# MMC_2_2_Ethernet.net
KiCad netlist of a schematic drawn in Altium Designer
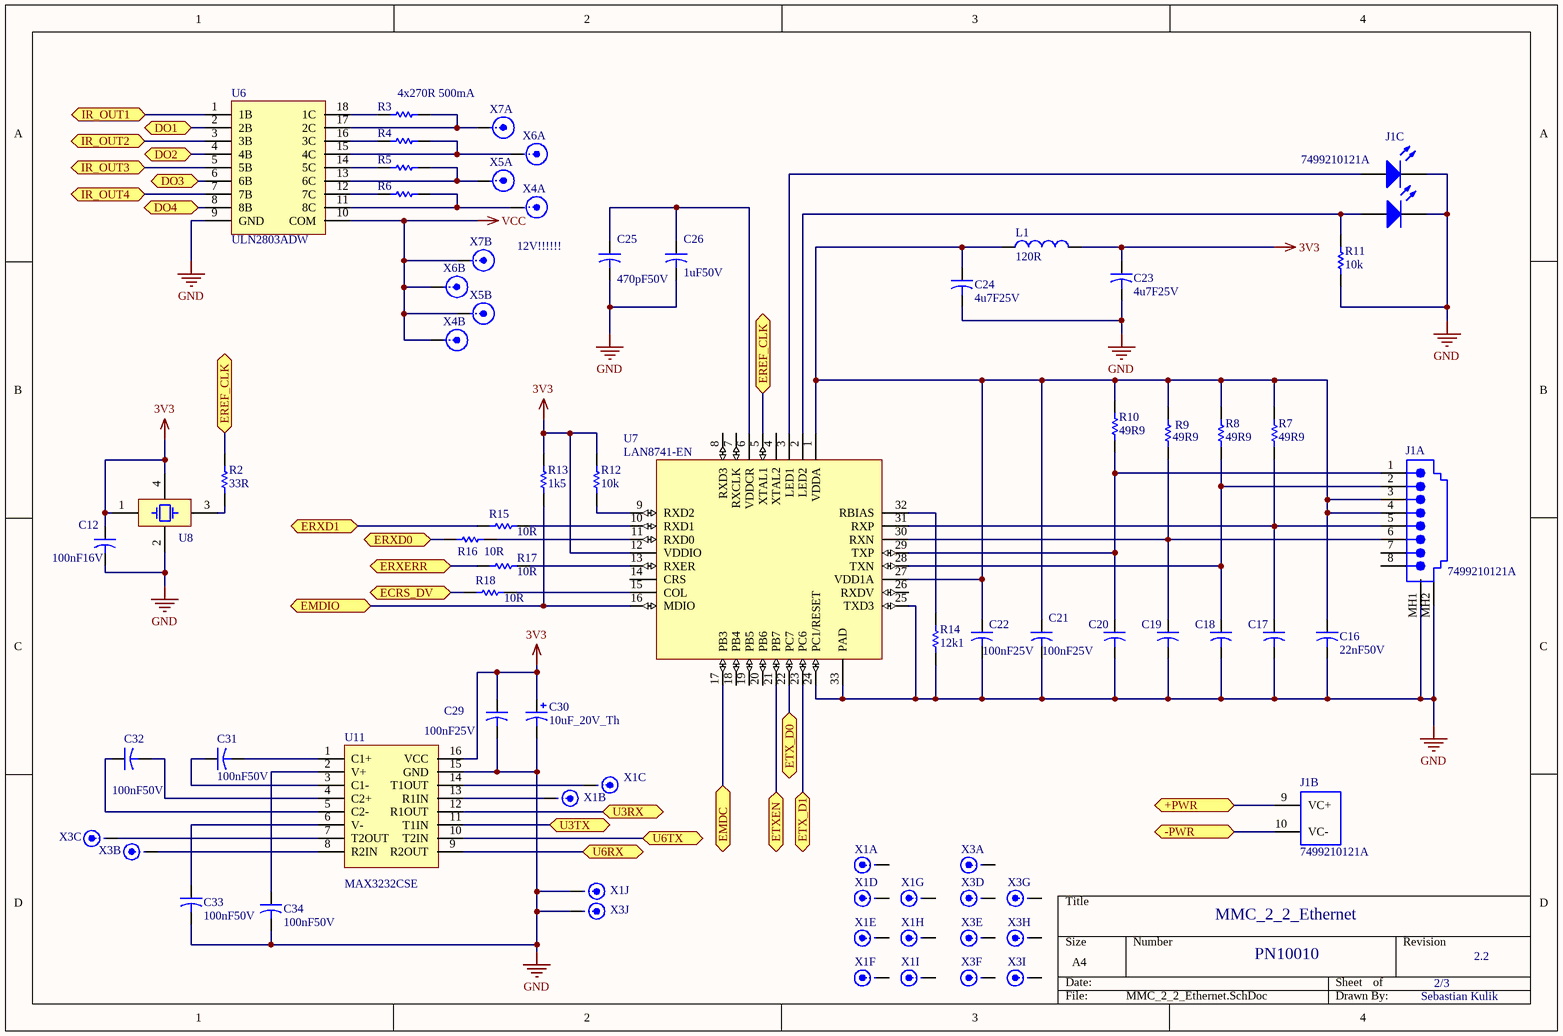
[diagram p0: MMC_2_2_Ethernet.SchDoc]

(export (version "E")
  (design (tool "Eeschema 10.0.6"))
  (components
    (comp (ref "C12")
      (value "100nF16V")
      (footprint "C0402")
      (description "Capacitor")
      (fields
        (field (name "MANUFACTURER") "TDK")
        (field (name "Comment") "100nF16V_0402")
        (field (name "PUBLISHER") "Sebastian Kulik")
      )
      (libsource (lib "Capacitors") (part "100nF16V_0402"))
    )
    (comp (ref "C16")
      (value "22nF50V")
      (footprint "C0603")
      (description "AVX ,  X7R, 5%, 50V")
      (fields
        (field (name "MANUFACTURER") "AVX")
        (field (name "Comment") "22nF50V_0603")
        (field (name "PUBLISHER") "Sebastian Kulik")
      )
      (libsource (lib "Capacitors") (part "22nF50V_0603"))
    )
    (comp (ref "C17")
      (value "10pF50V_0603")
      (footprint "C0603")
      (description "AVX ,  +-0.5pF, 50V")
      (fields (field (name "MANUFACTURER") "AVX") (field (name "PUBLISHER") "Sebastian Kulik"))
      (libsource (lib "Capacitors") (part "10pF50V_0603"))
    )
    (comp (ref "C18")
      (value "10pF50V_0603")
      (footprint "C0603")
      (description "AVX ,  +-0.5pF, 50V")
      (fields (field (name "MANUFACTURER") "AVX") (field (name "PUBLISHER") "Sebastian Kulik"))
      (libsource (lib "Capacitors") (part "10pF50V_0603"))
    )
    (comp (ref "C19")
      (value "10pF50V_0603")
      (footprint "C0603")
      (description "AVX ,  +-0.5pF, 50V")
      (fields (field (name "MANUFACTURER") "AVX") (field (name "PUBLISHER") "Sebastian Kulik"))
      (libsource (lib "Capacitors") (part "10pF50V_0603"))
    )
    (comp (ref "C20")
      (value "10pF50V_0603")
      (footprint "C0603")
      (description "AVX ,  +-0.5pF, 50V")
      (fields (field (name "MANUFACTURER") "AVX") (field (name "PUBLISHER") "Sebastian Kulik"))
      (libsource (lib "Capacitors") (part "10pF50V_0603"))
    )
    (comp (ref "C21")
      (value "100nF25V")
      (footprint "C0402")
      (description "AVX, X5R, 10%, 25V")
      (fields
        (field (name "MANUFACTURER") "AVX")
        (field (name "Comment") "100nF25V_0402")
        (field (name "PUBLISHER") "Sebastian Kulik")
      )
      (libsource (lib "Capacitors") (part "100nF25V_0402"))
    )
    (comp (ref "C22")
      (value "100nF25V")
      (footprint "C0402")
      (description "AVX, X5R, 10%, 25V")
      (fields
        (field (name "MANUFACTURER") "AVX")
        (field (name "Comment") "100nF25V_0402")
        (field (name "PUBLISHER") "Sebastian Kulik")
      )
      (libsource (lib "Capacitors") (part "100nF25V_0402"))
    )
    (comp (ref "C23")
      (value "4u7F25V")
      (footprint "C0805")
      (description "TDK  C series, X7R, 10%, 25V")
      (fields
        (field (name "MANUFACTURER") "TDK")
        (field (name "Comment") "4u7F25V_0805")
        (field (name "PUBLISHER") "Sebastian Kulik")
      )
      (libsource (lib "Capacitors") (part "4u7F25V_0805"))
    )
    (comp (ref "C24")
      (value "4u7F25V")
      (footprint "C0805")
      (description "TDK  C series, X7R, 10%, 25V")
      (fields
        (field (name "MANUFACTURER") "TDK")
        (field (name "Comment") "4u7F25V_0805")
        (field (name "PUBLISHER") "Sebastian Kulik")
      )
      (libsource (lib "Capacitors") (part "4u7F25V_0805"))
    )
    (comp (ref "C25")
      (value "470pF50V")
      (footprint "C0402")
      (description "AVX, 50V")
      (fields
        (field (name "MANUFACTURER") "AVX")
        (field (name "Comment") "470pF50V_0402")
        (field (name "PUBLISHER") "Sebastian Kulik")
      )
      (libsource (lib "Capacitors") (part "470pF50V_0402"))
    )
    (comp (ref "C26")
      (value "1uF50V")
      (footprint "C0603")
      (description "C series, X5R, 10%")
      (fields
        (field (name "MANUFACTURER") "TDK")
        (field (name "Comment") "1uF50V_0603")
        (field (name "PUBLISHER") "Sebastian Kulik")
      )
      (libsource (lib "Capacitors") (part "1uF50V_0603"))
    )
    (comp (ref "C29")
      (value "100nF25V")
      (footprint "C0402")
      (description "AVX, X5R, 10%, 25V")
      (fields
        (field (name "MANUFACTURER") "AVX")
        (field (name "Comment") "100nF25V_0402")
        (field (name "PUBLISHER") "Sebastian Kulik")
      )
      (libsource (lib "Capacitors") (part "100nF25V_0402"))
    )
    (comp (ref "C30")
      (value "10uF_20V_Th")
      (footprint "Vishay293D-B")
      (description "293 series, tantal, 10%, 10V")
      (fields
        (field (name "MANUFACTURER") "Vishay")
        (field (name "Comment") "10uF_20V_V293D-B")
        (field (name "PUBLISHER") "Sebastian Kulik")
      )
      (libsource (lib "Capacitors") (part "10uF_20V_V293D-B"))
    )
    (comp (ref "C31")
      (value "100nF50V")
      (footprint "C0402")
      (description "C series, X5R, 10%, 50V")
      (fields
        (field (name "MANUFACTURER") "TDK")
        (field (name "Comment") "100n50V_0402")
        (field (name "PUBLISHER") "Sebastian Kulik")
      )
      (libsource (lib "Capacitors") (part "100n50V_0402"))
    )
    (comp (ref "C32")
      (value "100nF50V")
      (footprint "C0402")
      (description "C series, X5R, 10%, 50V")
      (fields
        (field (name "MANUFACTURER") "TDK")
        (field (name "Comment") "100n50V_0402")
        (field (name "PUBLISHER") "Sebastian Kulik")
      )
      (libsource (lib "Capacitors") (part "100n50V_0402"))
    )
    (comp (ref "C33")
      (value "100nF50V")
      (footprint "C0402")
      (description "C series, X5R, 10%, 50V")
      (fields
        (field (name "MANUFACTURER") "TDK")
        (field (name "Comment") "100n50V_0402")
        (field (name "PUBLISHER") "Sebastian Kulik")
      )
      (libsource (lib "Capacitors") (part "100n50V_0402"))
    )
    (comp (ref "C34")
      (value "100nF50V")
      (footprint "C0402")
      (description "C series, X5R, 10%, 50V")
      (fields
        (field (name "MANUFACTURER") "TDK")
        (field (name "Comment") "100n50V_0402")
        (field (name "PUBLISHER") "Sebastian Kulik")
      )
      (libsource (lib "Capacitors") (part "100n50V_0402"))
    )
    (comp (ref "J1")
      (value "7499210121A")
      (footprint "7499210121A")
      (description "Modular Jack , Right Angle RJ-45, Low Profile")
      (fields (field (name "MANUFACTURER") "Wuerth Elektronik") (field (name "PUBLISHER") "Sebastian Kulik"))
      (libsource (lib "Connectors") (part "Ethernet, POE, WE7499210121A"))
    )
    (comp (ref "L1")
      (value "120R")
      (footprint "L0603")
      (description "Murata, Ferrit, 120Rx2A")
      (fields
        (field (name "MANUFACTURER") "Murata")
        (field (name "Comment") "120R4A_0603")
        (field (name "PUBLISHER") "Sebastian Kulik")
      )
      (libsource (lib "Passives") (part "120R4A_0603"))
    )
    (comp (ref "R2")
      (value "33R")
      (footprint "R0402")
      (description "Vishay CRCW series, 63mW, 1%")
      (fields
        (field (name "MANUFACTURER") "Vishay")
        (field (name "Comment") "33R_0402")
        (field (name "PUBLISHER") "Sebastian Kulik")
      )
      (libsource (lib "Resistors") (part "33R_0402"))
    )
    (comp (ref "R3")
      (value "270R_1210")
      (footprint "R1210_N")
      (description "ERJ series, 500mW, 5%")
      (fields (field (name "MANUFACTURER") "Panasonic") (field (name "PUBLISHER") "Sebastian Kulik"))
      (libsource (lib "Resistors") (part "270R_1210"))
    )
    (comp (ref "R4")
      (value "270R_1210")
      (footprint "R1210_N")
      (description "ERJ series, 500mW, 5%")
      (fields (field (name "MANUFACTURER") "Panasonic") (field (name "PUBLISHER") "Sebastian Kulik"))
      (libsource (lib "Resistors") (part "270R_1210"))
    )
    (comp (ref "R5")
      (value "270R_1210")
      (footprint "R1210_N")
      (description "ERJ series, 500mW, 5%")
      (fields (field (name "MANUFACTURER") "Panasonic") (field (name "PUBLISHER") "Sebastian Kulik"))
      (libsource (lib "Resistors") (part "270R_1210"))
    )
    (comp (ref "R6")
      (value "270R_1210")
      (footprint "R1210_N")
      (description "ERJ series, 500mW, 5%")
      (fields (field (name "MANUFACTURER") "Panasonic") (field (name "PUBLISHER") "Sebastian Kulik"))
      (libsource (lib "Resistors") (part "270R_1210"))
    )
    (comp (ref "R7")
      (value "49R9")
      (footprint "R0402")
      (description "Vishay CRCW series, 63mW, 1%")
      (fields
        (field (name "MANUFACTURER") "Vishay")
        (field (name "Comment") "49R9_0402")
        (field (name "PUBLISHER") "Sebastian Kulik")
      )
      (libsource (lib "Resistors") (part "49R9_0402"))
    )
    (comp (ref "R8")
      (value "49R9")
      (footprint "R0402")
      (description "Vishay CRCW series, 63mW, 1%")
      (fields
        (field (name "MANUFACTURER") "Vishay")
        (field (name "Comment") "49R9_0402")
        (field (name "PUBLISHER") "Sebastian Kulik")
      )
      (libsource (lib "Resistors") (part "49R9_0402"))
    )
    (comp (ref "R9")
      (value "49R9")
      (footprint "R0402")
      (description "Vishay CRCW series, 63mW, 1%")
      (fields
        (field (name "MANUFACTURER") "Vishay")
        (field (name "Comment") "49R9_0402")
        (field (name "PUBLISHER") "Sebastian Kulik")
      )
      (libsource (lib "Resistors") (part "49R9_0402"))
    )
    (comp (ref "R10")
      (value "49R9")
      (footprint "R0402")
      (description "Vishay CRCW series, 63mW, 1%")
      (fields
        (field (name "MANUFACTURER") "Vishay")
        (field (name "Comment") "49R9_0402")
        (field (name "PUBLISHER") "Sebastian Kulik")
      )
      (libsource (lib "Resistors") (part "49R9_0402"))
    )
    (comp (ref "R11")
      (value "10k")
      (footprint "R0402")
      (description "Vishay CRCW series, 125mW, 1%")
      (fields
        (field (name "MANUFACTURER") "Vishay")
        (field (name "Comment") "10k_0402")
        (field (name "PUBLISHER") "Sebastian Kulik")
      )
      (libsource (lib "Resistors") (part "10k_0402"))
    )
    (comp (ref "R12")
      (value "10k")
      (footprint "R0402")
      (description "Vishay CRCW series, 125mW, 1%")
      (fields
        (field (name "MANUFACTURER") "Vishay")
        (field (name "Comment") "10k_0402")
        (field (name "PUBLISHER") "Sebastian Kulik")
      )
      (libsource (lib "Resistors") (part "10k_0402"))
    )
    (comp (ref "R13")
      (value "1k5")
      (footprint "R0402")
      (description "Vishay CRCW series, 125mW, 1%")
      (fields
        (field (name "MANUFACTURER") "Vishay")
        (field (name "Comment") "1k5_0402")
        (field (name "PUBLISHER") "Sebastian Kulik")
      )
      (libsource (lib "Resistors") (part "1k5_0402"))
    )
    (comp (ref "R14")
      (value "12k1")
      (footprint "R0603(1608)")
      (description "Vishay, CRCW series, 100mW, 1%")
      (fields
        (field (name "MANUFACTURER") "Vishay")
        (field (name "Comment") "12k1_0603")
        (field (name "PUBLISHER") "Sebastian Kulik")
      )
      (libsource (lib "Resistors") (part "12k1_0603"))
    )
    (comp (ref "R15")
      (value "10R")
      (footprint "R0402")
      (description "Vishay CRCW series, 125mW, 1%")
      (fields
        (field (name "MANUFACTURER") "Vishay")
        (field (name "Comment") "10R_0402")
        (field (name "PUBLISHER") "Sebastian Kulik")
      )
      (libsource (lib "Resistors") (part "10R_0402"))
    )
    (comp (ref "R16")
      (value "10R")
      (footprint "R0402")
      (description "Vishay CRCW series, 125mW, 1%")
      (fields
        (field (name "MANUFACTURER") "Vishay")
        (field (name "Comment") "10R_0402")
        (field (name "PUBLISHER") "Sebastian Kulik")
      )
      (libsource (lib "Resistors") (part "10R_0402"))
    )
    (comp (ref "R17")
      (value "10R")
      (footprint "R0402")
      (description "Vishay CRCW series, 125mW, 1%")
      (fields
        (field (name "MANUFACTURER") "Vishay")
        (field (name "Comment") "10R_0402")
        (field (name "PUBLISHER") "Sebastian Kulik")
      )
      (libsource (lib "Resistors") (part "10R_0402"))
    )
    (comp (ref "R18")
      (value "10R")
      (footprint "R0402")
      (description "Vishay CRCW series, 125mW, 1%")
      (fields
        (field (name "MANUFACTURER") "Vishay")
        (field (name "Comment") "10R_0402")
        (field (name "PUBLISHER") "Sebastian Kulik")
      )
      (libsource (lib "Resistors") (part "10R_0402"))
    )
    (comp (ref "U6")
      (value "ULN2803ADW")
      (footprint "SOIC18-WIDE")
      (description "Darlington array, 50V")
      (fields (field (name "MANUFACTURER") "TI") (field (name "PUBLISHER") "Sebastian Kulik"))
      (libsource (lib "ICs") (part "ULN2803ADW"))
    )
    (comp (ref "U7")
      (value "LAN8741-EN")
      (footprint "32M1-A_M")
      (description "Ethernet Phy")
      (fields (field (name "MANUFACTURER") "Microchip") (field (name "PUBLISHER") "Sebastian Kulik"))
      (libsource (lib "ICs") (part "LAN8741-EN"))
    )
    (comp (ref "U8")
      (value "TXC-7W-50.000MBB-T")
      (footprint "TXC_7W")
      (description "Crystal")
      (fields (field (name "MANUFACTURER") "TXC") (field (name "PUBLISHER") "Sebastian Kulik"))
      (libsource (lib "ICs") (part "TXC-7W-50.000MBB-T"))
    )
    (comp (ref "U11")
      (value "MAX3232CSE")
      (footprint "SOIC16_L")
      (description "RS232 transceiver")
      (fields (field (name "MANUFACTURER") "Maxim") (field (name "PUBLISHER") "Sebastian Kulik"))
      (libsource (lib "ICs") (part "MAX3232CSE"))
    )
    (comp (ref "X1")
      (value "SUB-D_9")
      (footprint "M09HP")
      (fields (field (name "MANUFACTURER") "AMP") (field (name "PUBLISHER") "Sebastian Kulik"))
      (libsource (lib "Connectors") (part "SUB-D_9"))
    )
    (comp (ref "X3")
      (value "SUB-D_9")
      (footprint "M09HP")
      (fields (field (name "MANUFACTURER") "AMP") (field (name "PUBLISHER") "Sebastian Kulik"))
      (libsource (lib "Connectors") (part "SUB-D_9"))
    )
    (comp (ref "X4")
      (value "PhoenixMSTBA-2")
      (footprint "MSTBA 2,5_2-G-5,08-LR")
      (fields (field (name "MANUFACTURER") "Phoenix Contact") (field (name "PUBLISHER") "Sebastian Kulik"))
      (libsource (lib "") (part "PhoenixMSTBA-2_1"))
    )
    (comp (ref "X5")
      (value "PhoenixMSTBA-2")
      (footprint "MSTBA 2,5_2-G-5,08-LR")
      (fields (field (name "MANUFACTURER") "Phoenix Contact") (field (name "PUBLISHER") "Sebastian Kulik"))
      (libsource (lib "Connectors") (part "PhoenixMSTBA-2"))
    )
    (comp (ref "X6")
      (value "PhoenixMSTBA-2")
      (footprint "MSTBA 2,5_2-G-5,08-LR")
      (fields (field (name "MANUFACTURER") "Phoenix Contact") (field (name "PUBLISHER") "Sebastian Kulik"))
      (libsource (lib "") (part "PhoenixMSTBA-2_1"))
    )
    (comp (ref "X7")
      (value "PhoenixMSTBA-2")
      (footprint "MSTBA 2,5_2-G-5,08-LR")
      (fields (field (name "MANUFACTURER") "Phoenix Contact") (field (name "PUBLISHER") "Sebastian Kulik"))
      (libsource (lib "Connectors") (part "PhoenixMSTBA-2"))
    )
  )
  (nets
    (net (code "1") (name "/+PWR") (class "Default")
      (node (ref "J1") (pin "9") (pinfunction "VC+_9") (pintype "passive"))
    )
    (net (code "2") (name "/-PWR") (class "Default")
      (node (ref "J1") (pin "10") (pinfunction "VC-_10") (pintype "passive"))
    )
    (net (code "3") (name "/DO1") (class "Default")
      (node (ref "U6") (pin "2") (pinfunction "2B_2") (pintype "passive"))
    )
    (net (code "4") (name "/DO2") (class "Default")
      (node (ref "U6") (pin "4") (pinfunction "4B_4") (pintype "passive"))
    )
    (net (code "5") (name "/DO3") (class "Default")
      (node (ref "U6") (pin "6") (pinfunction "6B_6") (pintype "passive"))
    )
    (net (code "6") (name "/DO4") (class "Default")
      (node (ref "U6") (pin "8") (pinfunction "8B_8") (pintype "passive"))
    )
    (net (code "7") (name "/ECRS_DV") (class "Default")
      (node (ref "R18") (pin "2") (pinfunction "2_2") (pintype "passive"))
    )
    (net (code "8") (name "/EMDC") (class "Default")
      (node (ref "U7") (pin "17") (pinfunction "PB3_17") (pintype "bidirectional"))
    )
    (net (code "9") (name "/EMDIO") (class "Default")
      (node (ref "R13") (pin "1") (pinfunction "1_1") (pintype "passive"))
      (node (ref "U7") (pin "16") (pinfunction "MDIO_16") (pintype "bidirectional"))
    )
    (net (code "10") (name "/EREF_CLK") (class "Default")
      (node (ref "R2") (pin "2") (pinfunction "2_2") (pintype "passive"))
      (node (ref "U7") (pin "5") (pinfunction "XTAL1_5") (pintype "bidirectional"))
    )
    (net (code "11") (name "/ERXD0") (class "Default")
      (node (ref "R16") (pin "2") (pinfunction "2_2") (pintype "passive"))
    )
    (net (code "12") (name "/ERXD1") (class "Default")
      (node (ref "R15") (pin "2") (pinfunction "2_2") (pintype "passive"))
    )
    (net (code "13") (name "/ERXERR") (class "Default")
      (node (ref "R17") (pin "2") (pinfunction "2_2") (pintype "passive"))
    )
    (net (code "14") (name "/ETXEN") (class "Default")
      (node (ref "U7") (pin "21") (pinfunction "PB7_21") (pintype "bidirectional"))
    )
    (net (code "15") (name "/ETX_D0") (class "Default")
      (node (ref "U7") (pin "22") (pinfunction "PC7_22") (pintype "bidirectional"))
    )
    (net (code "16") (name "/ETX_D1") (class "Default")
      (node (ref "U7") (pin "23") (pinfunction "PC6_23") (pintype "bidirectional"))
    )
    (net (code "17") (name "/IR_OUT1") (class "Default")
      (node (ref "U6") (pin "1") (pinfunction "1B_1") (pintype "passive"))
    )
    (net (code "18") (name "/IR_OUT2") (class "Default")
      (node (ref "U6") (pin "3") (pinfunction "3B_3") (pintype "passive"))
    )
    (net (code "19") (name "/IR_OUT3") (class "Default")
      (node (ref "U6") (pin "5") (pinfunction "5B_5") (pintype "passive"))
    )
    (net (code "20") (name "/IR_OUT4") (class "Default")
      (node (ref "U6") (pin "7") (pinfunction "7B_7") (pintype "passive"))
    )
    (net (code "21") (name "/U3RX") (class "Default")
      (node (ref "U11") (pin "12") (pinfunction "R1OUT_12") (pintype "passive"))
    )
    (net (code "22") (name "/U3TX") (class "Default")
      (node (ref "U11") (pin "11") (pinfunction "T1IN_11") (pintype "passive"))
    )
    (net (code "23") (name "/U6RX") (class "Default")
      (node (ref "U11") (pin "9") (pinfunction "R2OUT_9") (pintype "passive"))
    )
    (net (code "24") (name "/U6TX") (class "Default")
      (node (ref "U11") (pin "10") (pinfunction "T2IN_10") (pintype "passive"))
    )
    (net (code "25") (name "3V3") (class "Default")
      (node (ref "C12") (pin "1") (pinfunction "1_1") (pintype "passive"))
      (node (ref "C23") (pin "1") (pinfunction "1_1") (pintype "passive"))
      (node (ref "C29") (pin "1") (pinfunction "1_1") (pintype "passive"))
      (node (ref "C30") (pin "1") (pinfunction "1_1") (pintype "passive"))
      (node (ref "L1") (pin "2") (pinfunction "2_2") (pintype "passive"))
      (node (ref "R12") (pin "2") (pinfunction "2_2") (pintype "passive"))
      (node (ref "R13") (pin "2") (pinfunction "2_2") (pintype "passive"))
      (node (ref "U11") (pin "16") (pinfunction "VCC_16") (pintype "passive"))
      (node (ref "U7") (pin "12") (pinfunction "VDDIO_12") (pintype "passive"))
      (node (ref "U8") (pin "1") (pinfunction "E/D_1") (pintype "passive"))
      (node (ref "U8") (pin "4") (pinfunction "VCC_4") (pintype "passive"))
    )
    (net (code "26") (name "GND") (class "Default")
      (node (ref "C12") (pin "2") (pinfunction "2_2") (pintype "passive"))
      (node (ref "C16") (pin "2") (pinfunction "2_2") (pintype "passive"))
      (node (ref "C17") (pin "2") (pinfunction "2_2") (pintype "passive"))
      (node (ref "C18") (pin "2") (pinfunction "2_2") (pintype "passive"))
      (node (ref "C19") (pin "2") (pinfunction "2_2") (pintype "passive"))
      (node (ref "C20") (pin "2") (pinfunction "2_2") (pintype "passive"))
      (node (ref "C21") (pin "2") (pinfunction "2_2") (pintype "passive"))
      (node (ref "C22") (pin "2") (pinfunction "2_2") (pintype "passive"))
      (node (ref "C23") (pin "2") (pinfunction "2_2") (pintype "passive"))
      (node (ref "C24") (pin "2") (pinfunction "2_2") (pintype "passive"))
      (node (ref "C25") (pin "2") (pinfunction "2_2") (pintype "passive"))
      (node (ref "C26") (pin "2") (pinfunction "2_2") (pintype "passive"))
      (node (ref "C29") (pin "2") (pinfunction "2_2") (pintype "passive"))
      (node (ref "C30") (pin "2") (pinfunction "2_2") (pintype "passive"))
      (node (ref "C33") (pin "2") (pinfunction "2_2") (pintype "passive"))
      (node (ref "C34") (pin "2") (pinfunction "2_2") (pintype "passive"))
      (node (ref "J1") (pin "12") (pinfunction "K_12") (pintype "passive"))
      (node (ref "J1") (pin "14") (pinfunction "K_14") (pintype "passive"))
      (node (ref "J1") (pin "MH1") (pinfunction "Shield_MH1") (pintype "passive"))
      (node (ref "J1") (pin "MH2") (pinfunction "Shield_MH2") (pintype "passive"))
      (node (ref "R11") (pin "1") (pinfunction "1_1") (pintype "passive"))
      (node (ref "R14") (pin "1") (pinfunction "1_1") (pintype "passive"))
      (node (ref "U11") (pin "15") (pinfunction "GND_15") (pintype "passive"))
      (node (ref "U6") (pin "9") (pinfunction "GND_9") (pintype "passive"))
      (node (ref "U7") (pin "24") (pinfunction "PC1/RESET_24") (pintype "bidirectional"))
      (node (ref "U7") (pin "25") (pinfunction "TXD3_25") (pintype "bidirectional"))
      (node (ref "U7") (pin "33") (pinfunction "PAD_33") (pintype "power_in"))
      (node (ref "U8") (pin "2") (pinfunction "GND_2") (pintype "passive"))
      (node (ref "X1") (pin "10") (pinfunction "GND_10") (pintype "passive"))
      (node (ref "X3") (pin "10") (pinfunction "GND_10") (pintype "passive"))
    )
    (net (code "27") (name "Net-(U6-1C)") (class "Default")
      (node (ref "R3") (pin "1") (pinfunction "1_1") (pintype "passive"))
      (node (ref "U6") (pin "18") (pinfunction "1C_18") (pintype "passive"))
    )
    (net (code "28") (name "Net-(U6-2C)") (class "Default")
      (node (ref "R3") (pin "2") (pinfunction "2_2") (pintype "passive"))
      (node (ref "U6") (pin "17") (pinfunction "2C_17") (pintype "passive"))
      (node (ref "X7") (pin "1") (pinfunction "X_1") (pintype "passive"))
    )
    (net (code "29") (name "Net-(U6-3C)") (class "Default")
      (node (ref "R4") (pin "1") (pinfunction "1_1") (pintype "passive"))
      (node (ref "U6") (pin "16") (pinfunction "3C_16") (pintype "passive"))
    )
    (net (code "30") (name "Net-(U6-4C)") (class "Default")
      (node (ref "R4") (pin "2") (pinfunction "2_2") (pintype "passive"))
      (node (ref "U6") (pin "15") (pinfunction "4C_15") (pintype "passive"))
      (node (ref "X6") (pin "1") (pinfunction "X_1") (pintype "passive"))
    )
    (net (code "31") (name "Net-(U6-5C)") (class "Default")
      (node (ref "R5") (pin "1") (pinfunction "1_1") (pintype "passive"))
      (node (ref "U6") (pin "14") (pinfunction "5C_14") (pintype "passive"))
    )
    (net (code "32") (name "Net-(U6-6C)") (class "Default")
      (node (ref "R5") (pin "2") (pinfunction "2_2") (pintype "passive"))
      (node (ref "U6") (pin "13") (pinfunction "6C_13") (pintype "passive"))
      (node (ref "X5") (pin "1") (pinfunction "X_1") (pintype "passive"))
    )
    (net (code "33") (name "Net-(U6-7C)") (class "Default")
      (node (ref "R6") (pin "1") (pinfunction "1_1") (pintype "passive"))
      (node (ref "U6") (pin "12") (pinfunction "7C_12") (pintype "passive"))
    )
    (net (code "34") (name "Net-(U6-8C)") (class "Default")
      (node (ref "R6") (pin "2") (pinfunction "2_2") (pintype "passive"))
      (node (ref "U6") (pin "11") (pinfunction "8C_11") (pintype "passive"))
      (node (ref "X4") (pin "1") (pinfunction "X_1") (pintype "passive"))
    )
    (net (code "35") (name "Net-(U7-COL)") (class "Default")
      (node (ref "R18") (pin "1") (pinfunction "1_1") (pintype "passive"))
      (node (ref "U7") (pin "15") (pinfunction "COL_15") (pintype "passive"))
    )
    (net (code "36") (name "Net-(U7-LED1)") (class "Default")
      (node (ref "J1") (pin "11") (pinfunction "A_11") (pintype "passive"))
      (node (ref "U7") (pin "3") (pinfunction "LED1_3") (pintype "power_in"))
    )
    (net (code "37") (name "Net-(U7-LED2)") (class "Default")
      (node (ref "J1") (pin "13") (pinfunction "A_13") (pintype "passive"))
      (node (ref "R11") (pin "2") (pinfunction "2_2") (pintype "passive"))
      (node (ref "U7") (pin "2") (pinfunction "LED2_2") (pintype "passive"))
    )
    (net (code "38") (name "Net-(U7-RBIAS)") (class "Default")
      (node (ref "R14") (pin "2") (pinfunction "2_2") (pintype "passive"))
      (node (ref "U7") (pin "32") (pinfunction "RBIAS_32") (pintype "power_in"))
    )
    (net (code "39") (name "Net-(U7-RXD0)") (class "Default")
      (node (ref "R16") (pin "1") (pinfunction "1_1") (pintype "passive"))
      (node (ref "U7") (pin "11") (pinfunction "RXD0_11") (pintype "bidirectional"))
    )
    (net (code "40") (name "Net-(U7-RXD1)") (class "Default")
      (node (ref "R15") (pin "1") (pinfunction "1_1") (pintype "passive"))
      (node (ref "U7") (pin "10") (pinfunction "RXD1_10") (pintype "bidirectional"))
    )
    (net (code "41") (name "Net-(U7-RXD2)") (class "Default")
      (node (ref "R12") (pin "1") (pinfunction "1_1") (pintype "passive"))
      (node (ref "U7") (pin "9") (pinfunction "RXD2_9") (pintype "bidirectional"))
    )
    (net (code "42") (name "Net-(U7-RXER)") (class "Default")
      (node (ref "R17") (pin "1") (pinfunction "1_1") (pintype "passive"))
      (node (ref "U7") (pin "13") (pinfunction "RXER_13") (pintype "bidirectional"))
    )
    (net (code "43") (name "Net-(U7-RXN)") (class "Default")
      (node (ref "C19") (pin "1") (pinfunction "1_1") (pintype "passive"))
      (node (ref "J1") (pin "6") (pinfunction "6_6") (pintype "passive"))
      (node (ref "R9") (pin "1") (pinfunction "1_1") (pintype "passive"))
      (node (ref "U7") (pin "30") (pinfunction "RXN_30") (pintype "passive"))
    )
    (net (code "44") (name "Net-(U7-RXP)") (class "Default")
      (node (ref "C17") (pin "1") (pinfunction "1_1") (pintype "passive"))
      (node (ref "J1") (pin "5") (pinfunction "5_5") (pintype "passive"))
      (node (ref "R7") (pin "1") (pinfunction "1_1") (pintype "passive"))
      (node (ref "U7") (pin "31") (pinfunction "RXP_31") (pintype "passive"))
    )
    (net (code "45") (name "Net-(U7-TXN)") (class "Default")
      (node (ref "C18") (pin "1") (pinfunction "1_1") (pintype "passive"))
      (node (ref "J1") (pin "2") (pinfunction "2_2") (pintype "passive"))
      (node (ref "R8") (pin "1") (pinfunction "1_1") (pintype "passive"))
      (node (ref "U7") (pin "28") (pinfunction "TXN_28") (pintype "bidirectional"))
    )
    (net (code "46") (name "Net-(U7-TXP)") (class "Default")
      (node (ref "C20") (pin "1") (pinfunction "1_1") (pintype "passive"))
      (node (ref "J1") (pin "1") (pinfunction "1_1") (pintype "passive"))
      (node (ref "R10") (pin "1") (pinfunction "1_1") (pintype "passive"))
      (node (ref "U7") (pin "29") (pinfunction "TXP_29") (pintype "bidirectional"))
    )
    (net (code "47") (name "Net-(U7-VDD1A)") (class "Default")
      (node (ref "C16") (pin "1") (pinfunction "1_1") (pintype "passive"))
      (node (ref "C21") (pin "1") (pinfunction "1_1") (pintype "passive"))
      (node (ref "C22") (pin "1") (pinfunction "1_1") (pintype "passive"))
      (node (ref "C24") (pin "1") (pinfunction "1_1") (pintype "passive"))
      (node (ref "J1") (pin "3") (pinfunction "3_3") (pintype "passive"))
      (node (ref "J1") (pin "4") (pinfunction "4_4") (pintype "passive"))
      (node (ref "L1") (pin "1") (pinfunction "1_1") (pintype "passive"))
      (node (ref "R10") (pin "2") (pinfunction "2_2") (pintype "passive"))
      (node (ref "R7") (pin "2") (pinfunction "2_2") (pintype "passive"))
      (node (ref "R8") (pin "2") (pinfunction "2_2") (pintype "passive"))
      (node (ref "R9") (pin "2") (pinfunction "2_2") (pintype "passive"))
      (node (ref "U7") (pin "1") (pinfunction "VDDA_1") (pintype "passive"))
      (node (ref "U7") (pin "27") (pinfunction "VDD1A_27") (pintype "passive"))
    )
    (net (code "48") (name "Net-(U7-VDDCR)") (class "Default")
      (node (ref "C25") (pin "1") (pinfunction "1_1") (pintype "passive"))
      (node (ref "C26") (pin "1") (pinfunction "1_1") (pintype "passive"))
      (node (ref "U7") (pin "6") (pinfunction "VDDCR_6") (pintype "passive"))
    )
    (net (code "49") (name "Net-(U8-OSC2)") (class "Default")
      (node (ref "R2") (pin "1") (pinfunction "1_1") (pintype "passive"))
      (node (ref "U8") (pin "3") (pinfunction "OSC2_3") (pintype "passive"))
    )
    (net (code "50") (name "Net-(U11-C1+)") (class "Default")
      (node (ref "C31") (pin "2") (pinfunction "2_2") (pintype "passive"))
      (node (ref "U11") (pin "1") (pinfunction "C1+_1") (pintype "passive"))
    )
    (net (code "51") (name "Net-(U11-C1-)") (class "Default")
      (node (ref "C31") (pin "1") (pinfunction "1_1") (pintype "passive"))
      (node (ref "U11") (pin "3") (pinfunction "C1-_3") (pintype "passive"))
    )
    (net (code "52") (name "Net-(U11-C2+)") (class "Default")
      (node (ref "C32") (pin "2") (pinfunction "2_2") (pintype "passive"))
      (node (ref "U11") (pin "4") (pinfunction "C2+_4") (pintype "passive"))
    )
    (net (code "53") (name "Net-(U11-C2-)") (class "Default")
      (node (ref "C32") (pin "1") (pinfunction "1_1") (pintype "passive"))
      (node (ref "U11") (pin "5") (pinfunction "C2-_5") (pintype "passive"))
    )
    (net (code "54") (name "Net-(U11-R1IN)") (class "Default")
      (node (ref "U11") (pin "13") (pinfunction "R1IN_13") (pintype "passive"))
      (node (ref "X1") (pin "2") (pintype "passive"))
    )
    (net (code "55") (name "Net-(U11-R2IN)") (class "Default")
      (node (ref "U11") (pin "8") (pinfunction "R2IN_8") (pintype "passive"))
      (node (ref "X3") (pin "2") (pintype "passive"))
    )
    (net (code "56") (name "Net-(U11-T1OUT)") (class "Default")
      (node (ref "U11") (pin "14") (pinfunction "T1OUT_14") (pintype "passive"))
      (node (ref "X1") (pin "3") (pintype "passive"))
    )
    (net (code "57") (name "Net-(U11-T2OUT)") (class "Default")
      (node (ref "U11") (pin "7") (pinfunction "T2OUT_7") (pintype "passive"))
      (node (ref "X3") (pin "3") (pintype "passive"))
    )
    (net (code "58") (name "Net-(U11-V+)") (class "Default")
      (node (ref "C34") (pin "1") (pinfunction "1_1") (pintype "passive"))
      (node (ref "U11") (pin "2") (pinfunction "V+_2") (pintype "passive"))
    )
    (net (code "59") (name "Net-(U11-V-)") (class "Default")
      (node (ref "C33") (pin "1") (pinfunction "1_1") (pintype "passive"))
      (node (ref "U11") (pin "6") (pinfunction "V-_6") (pintype "passive"))
    )
    (net (code "60") (name "VCC") (class "Default")
      (node (ref "U6") (pin "10") (pinfunction "COM_10") (pintype "passive"))
      (node (ref "X4") (pin "2") (pinfunction "Y_2") (pintype "passive"))
      (node (ref "X5") (pin "2") (pinfunction "Y_2") (pintype "passive"))
      (node (ref "X6") (pin "2") (pinfunction "Y_2") (pintype "passive"))
      (node (ref "X7") (pin "2") (pinfunction "Y_2") (pintype "passive"))
    )
    (net (code "61") (name "unconnected-(J1-Pad7)") (class "Default")
      (node (ref "J1") (pin "7") (pinfunction "7_7") (pintype "passive"))
    )
    (net (code "62") (name "unconnected-(J1-Pad8)") (class "Default")
      (node (ref "J1") (pin "8") (pinfunction "8_8") (pintype "passive"))
    )
    (net (code "63") (name "unconnected-(U7-CRS-Pad14)") (class "Default")
      (node (ref "U7") (pin "14") (pinfunction "CRS_14") (pintype "passive"))
    )
    (net (code "64") (name "unconnected-(U7-PB4-Pad18)") (class "Default")
      (node (ref "U7") (pin "18") (pinfunction "PB4_18") (pintype "bidirectional"))
    )
    (net (code "65") (name "unconnected-(U7-PB5-Pad19)") (class "Default")
      (node (ref "U7") (pin "19") (pinfunction "PB5_19") (pintype "bidirectional"))
    )
    (net (code "66") (name "unconnected-(U7-PB6-Pad20)") (class "Default")
      (node (ref "U7") (pin "20") (pinfunction "PB6_20") (pintype "bidirectional"))
    )
    (net (code "67") (name "unconnected-(U7-RXCLK-Pad7)") (class "Default")
      (node (ref "U7") (pin "7") (pinfunction "RXCLK_7") (pintype "bidirectional"))
    )
    (net (code "68") (name "unconnected-(U7-RXD3-Pad8)") (class "Default")
      (node (ref "U7") (pin "8") (pinfunction "RXD3_8") (pintype "bidirectional"))
    )
    (net (code "69") (name "unconnected-(U7-RXDV-Pad26)") (class "Default")
      (node (ref "U7") (pin "26") (pinfunction "RXDV_26") (pintype "bidirectional"))
    )
    (net (code "70") (name "unconnected-(U7-XTAL2-Pad4)") (class "Default")
      (node (ref "U7") (pin "4") (pinfunction "XTAL2_4") (pintype "power_in"))
    )
    (net (code "71") (name "unconnected-(X1-Pad1)") (class "Default")
      (node (ref "X1") (pin "1") (pintype "passive"))
    )
    (net (code "72") (name "unconnected-(X1-Pad4)") (class "Default")
      (node (ref "X1") (pin "4") (pintype "passive"))
    )
    (net (code "73") (name "unconnected-(X1-Pad5)") (class "Default")
      (node (ref "X1") (pin "5") (pintype "passive"))
    )
    (net (code "74") (name "unconnected-(X1-Pad6)") (class "Default")
      (node (ref "X1") (pin "6") (pintype "passive"))
    )
    (net (code "75") (name "unconnected-(X1-Pad7)") (class "Default")
      (node (ref "X1") (pin "7") (pintype "passive"))
    )
    (net (code "76") (name "unconnected-(X1-Pad8)") (class "Default")
      (node (ref "X1") (pin "8") (pintype "passive"))
    )
    (net (code "77") (name "unconnected-(X1-Pad9)") (class "Default")
      (node (ref "X1") (pin "9") (pintype "passive"))
    )
    (net (code "78") (name "unconnected-(X3-Pad1)") (class "Default")
      (node (ref "X3") (pin "1") (pintype "passive"))
    )
    (net (code "79") (name "unconnected-(X3-Pad4)") (class "Default")
      (node (ref "X3") (pin "4") (pintype "passive"))
    )
    (net (code "80") (name "unconnected-(X3-Pad5)") (class "Default")
      (node (ref "X3") (pin "5") (pintype "passive"))
    )
    (net (code "81") (name "unconnected-(X3-Pad6)") (class "Default")
      (node (ref "X3") (pin "6") (pintype "passive"))
    )
    (net (code "82") (name "unconnected-(X3-Pad7)") (class "Default")
      (node (ref "X3") (pin "7") (pintype "passive"))
    )
    (net (code "83") (name "unconnected-(X3-Pad8)") (class "Default")
      (node (ref "X3") (pin "8") (pintype "passive"))
    )
    (net (code "84") (name "unconnected-(X3-Pad9)") (class "Default")
      (node (ref "X3") (pin "9") (pintype "passive"))
    )
  )
)
